# Metroband_1_1_with_changes_-_Sheet1.net
KiCad netlist of a schematic drawn in Altium Designer
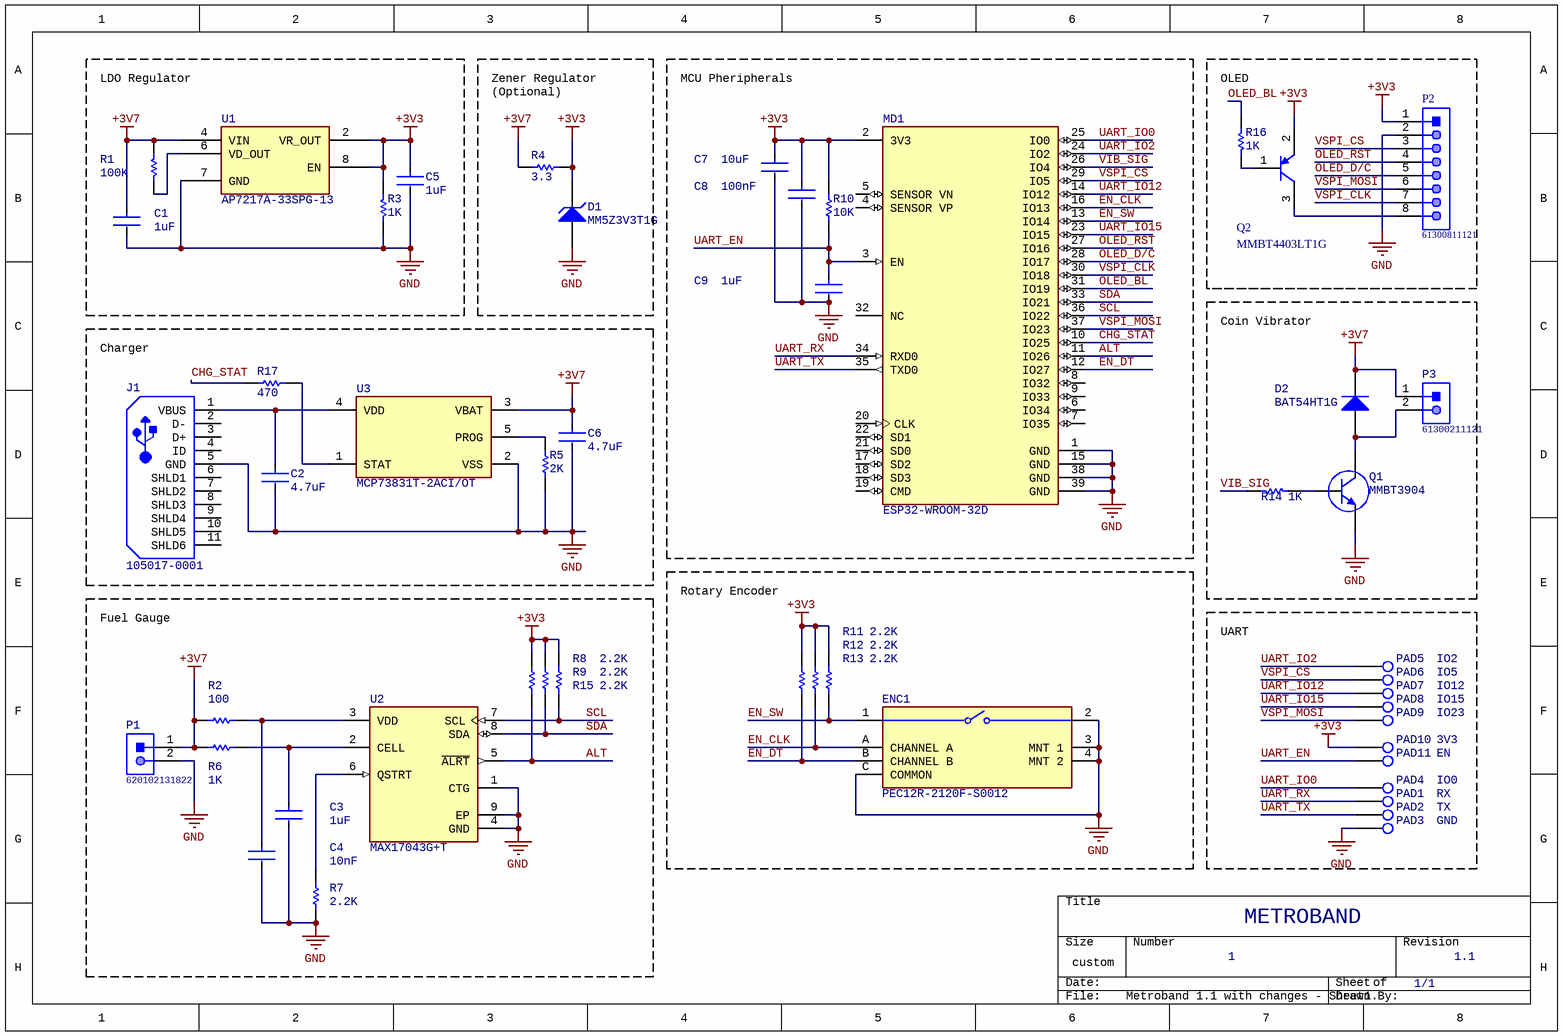
[diagram p0: Metroband 1.1 with changes - Sheet1.SchDoc]

(export (version "E")
  (design (tool "Eeschema 10.0.6"))
  (components
    (comp (ref "C1")
      (value "1uF")
      (footprint "FP-GRM21B-0_15-IPC_C")
      (description "Chip Multilayer Ceramic Capacitors for General Purpose, 0805, 1uF, X5R, 15%, 10%, 25V")
      (fields (field (name "VOLTAGE") "25V") (field (name "TOLERANCE") "10%"))
      (libsource (lib "Altium Content Vault") (part "b4654b650e69147ec39a6b967a45e02"))
    )
    (comp (ref "C2")
      (value "4.7uF")
      (footprint "FP-GRM21B-0_15-IPC_C")
      (description "Chip Multilayer Ceramic Capacitors for General Purpose, 0805, 4.7uF, X5R, 15%, 10%, 25V")
      (fields (field (name "VOLTAGE") "25V") (field (name "TOLERANCE") "10%"))
      (libsource (lib "Altium Content Vault") (part "b4654b650e69147ec39a6b967a45e02"))
    )
    (comp (ref "C3")
      (value "1uF")
      (footprint "FP-GRM21B-0_15-IPC_C")
      (description "Chip Multilayer Ceramic Capacitors for General Purpose, 0805, 1uF, X5R, 15%, 10%, 25V")
      (fields (field (name "VOLTAGE") "25V") (field (name "TOLERANCE") "10%"))
      (libsource (lib "Altium Content Vault") (part "b4654b650e69147ec39a6b967a45e02"))
    )
    (comp (ref "C4")
      (value "10nF")
      (footprint "FP-GRM21B-0_15-IPC_C")
      (description "Chip Multilayer Ceramic Capacitors for General Purpose, 0805, 10nF, X5R, 15%, 10%, 25V")
      (fields (field (name "VOLTAGE") "25V") (field (name "TOLERANCE") "10%"))
      (libsource (lib "Altium Content Vault") (part "b4654b650e69147ec39a6b967a45e02"))
    )
    (comp (ref "C5")
      (value "1uF")
      (footprint "FP-GRM21B-0_15-IPC_C")
      (description "Chip Multilayer Ceramic Capacitors for General Purpose, 0805, 1uF, X5R, 15%, 10%, 25V")
      (fields (field (name "VOLTAGE") "25V") (field (name "TOLERANCE") "10%"))
      (libsource (lib "Altium Content Vault") (part "b4654b650e69147ec39a6b967a45e02"))
    )
    (comp (ref "C6")
      (value "4.7uF")
      (footprint "FP-GRM21B-0_15-IPC_C")
      (description "Chip Multilayer Ceramic Capacitors for General Purpose, 0805, 4.7uF, X5R, 15%, 10%, 25V")
      (fields (field (name "VOLTAGE") "25V") (field (name "TOLERANCE") "10%"))
      (libsource (lib "Altium Content Vault") (part "b4654b650e69147ec39a6b967a45e02"))
    )
    (comp (ref "C7")
      (value "10uF")
      (footprint "FP-GRM21B-0_15-IPC_C")
      (description "Chip Multilayer Ceramic Capacitors for General Purpose, 0805, 10uF, X5R, 15%, 10%, 25V")
      (fields (field (name "VOLTAGE") "25V") (field (name "TOLERANCE") "10%"))
      (libsource (lib "Altium Content Vault") (part "b4654b650e69147ec39a6b967a45e02"))
    )
    (comp (ref "C8")
      (value "100nF")
      (footprint "FP-GRM21B-0_15-IPC_C")
      (description "Chip Multilayer Ceramic Capacitors for General Purpose, 0805, 100nF, X5R, 15%, 10%, 25V")
      (fields (field (name "VOLTAGE") "25V") (field (name "TOLERANCE") "10%"))
      (libsource (lib "Altium Content Vault") (part "b4654b650e69147ec39a6b967a45e02"))
    )
    (comp (ref "C9")
      (value "1uF")
      (footprint "FP-GRM21B-0_15-IPC_C")
      (description "Chip Multilayer Ceramic Capacitors for General Purpose, 0805, 1uF, X5R, 15%, 10%, 25V")
      (fields (field (name "VOLTAGE") "25V") (field (name "TOLERANCE") "10%"))
      (libsource (lib "Altium Content Vault") (part "b4654b650e69147ec39a6b967a45e02"))
    )
    (comp (ref "D1")
      (value "MM5Z3V3T1G")
      (footprint "ONSC-SOD-523-2-502-01_V")
      (description "Zener Voltage Regulator, 500 mW, 2-Pin SOD-523, Pb-Free, Tape and Reel")
      (fields (field (name "MANUFACTURER") "On Semiconductor"))
      (libsource (lib "Altium Content Vault") (part "ONSC-K1A2-2"))
    )
    (comp (ref "D2")
      (value "BAT54HT1G")
      (footprint "ONSC-SOD-323-2-477-02_V")
      (description "Schottky Barrier Diode, 2-Pin SOD-323, Pb-Free, Tape and Reel")
      (fields (field (name "MANUFACTURER") "On Semiconductor"))
      (libsource (lib "Altium Content Vault") (part "ONSC-D-K1A2-2"))
    )
    (comp (ref "ENC1")
      (value "PEC12R-2120F-S0012")
      (footprint "FP-PEC12R-2120F-S0012-MFG")
      (description "ROTARY ENCODER MECHANICAL 12PPR")
      (libsource (lib "Altium Content Vault") (part "b5b8d557d67ab9c2afb5dfea282e03e"))
    )
    (comp (ref "J1")
      (value "105017-0001")
      (footprint "USB-MICRO-B_V")
      (fields (field (name "MANUFACTURER") "Molex"))
      (libsource (lib "Altium Content Vault") (part "USB-5-6SHLD"))
    )
    (comp (ref "MD1")
      (value "ESP32-WROOM-32D")
      (footprint "FP-ESP32-WROOM-32D-MFG")
      (description "WIFI MODULE 32MBITS SPI FLASH")
      (fields
        (field (name "OCTOPART") "https://octopart.com/esp32-wroom-32d-espressif+systems-91040050")
        (field (name "MANUFACTURER") "Espressif Systems")
      )
      (libsource (lib "Altium Content Vault") (part "a031a76f8c27026a7a7f4657ff233a3"))
    )
    (comp (ref "P1")
      (value "620102131822")
      (footprint "620102131822")
      (description "Male Shrouded Header WR-WTB, SMT, Right Angled, pitch 2 mm, 1 x 2 position")
      (fields (field (name "MANUFACTURER") "Wurth Elektronik") (field (name "PUBLISHER") "WurthElektronik"))
      (libsource (lib "Altium Content Vault") (part "WE-CN-1P-M-R2"))
    )
    (comp (ref "P2")
      (value "61300811121")
      (footprint "61300811121")
      (description "THT Vertical Pin Header WR-PHD, Pitch 2.54 mm, Single Row, 8 pins")
      (fields (field (name "MANUFACTURER") "Wurth Elektronik") (field (name "PUBLISHER") "WurthElektronik"))
      (libsource (lib "Altium Content Vault") (part "WE-CN-1P-M-R8"))
    )
    (comp (ref "P3")
      (value "61300211121")
      (footprint "61300211121")
      (description "THT Vertical Pin Header WR-PHD, Pitch 2.54 mm, Single Row, 2 pins")
      (fields (field (name "MANUFACTURER") "Wurth Elektronik") (field (name "PUBLISHER") "WurthElektronik"))
      (libsource (lib "") (part "WE-CN-1P-M-R2_1"))
    )
    (comp (ref "PAD1")
      (value "RX")
      (footprint "PAD-Footprint-1")
      (description "Wirepad")
      (libsource (lib "UoM") (part "PAD-Symbol-1"))
    )
    (comp (ref "PAD2")
      (value "TX")
      (footprint "PAD-Footprint-1")
      (description "Wirepad")
      (libsource (lib "UoM") (part "PAD-Symbol-1"))
    )
    (comp (ref "PAD3")
      (value "GND")
      (footprint "PAD-Footprint-1")
      (description "Wirepad")
      (libsource (lib "UoM") (part "PAD-Symbol-1"))
    )
    (comp (ref "PAD4")
      (value "IO0")
      (footprint "PAD-Footprint-1")
      (description "Wirepad")
      (libsource (lib "UoM") (part "PAD-Symbol-1"))
    )
    (comp (ref "PAD5")
      (value "IO2")
      (footprint "PAD-Footprint-1")
      (description "Wirepad")
      (libsource (lib "UoM") (part "PAD-Symbol-1"))
    )
    (comp (ref "PAD6")
      (value "IO5")
      (footprint "PAD-Footprint-1")
      (description "Wirepad")
      (libsource (lib "UoM") (part "PAD-Symbol-1"))
    )
    (comp (ref "PAD7")
      (value "IO12")
      (footprint "PAD-Footprint-1")
      (description "Wirepad")
      (libsource (lib "UoM") (part "PAD-Symbol-1"))
    )
    (comp (ref "PAD8")
      (value "IO15")
      (footprint "PAD-Footprint-1")
      (description "Wirepad")
      (libsource (lib "UoM") (part "PAD-Symbol-1"))
    )
    (comp (ref "PAD9")
      (value "IO23")
      (footprint "PAD-Footprint-1")
      (description "Wirepad")
      (libsource (lib "UoM") (part "PAD-Symbol-1"))
    )
    (comp (ref "PAD10")
      (value "3V3")
      (footprint "PAD-Footprint-1")
      (description "Wirepad")
      (libsource (lib "UoM") (part "PAD-Symbol-1"))
    )
    (comp (ref "PAD11")
      (value "EN")
      (footprint "PAD-Footprint-1")
      (description "Wirepad")
      (libsource (lib "UoM") (part "PAD-Symbol-1"))
    )
    (comp (ref "Q1")
      (value "MMBT3904")
      (footprint "NXP-SOT23-3_V")
      (description "TRANSISTOR, NPN, REEL 3K")
      (libsource (lib "UoM") (part "TRANS-NPN-3"))
    )
    (comp (ref "Q2")
      (value "MMBT4403LT1G")
      (footprint "ONSC-SOT-23-3-318-08_V")
      (description "Switching Transistor, PNP Silicon, 3-Pin SOT-23, Pb-Free, Tape and Reel")
      (fields (field (name "MANUFACTURER") "On Semiconductor"))
      (libsource (lib "Altium Content Vault") (part "ONSC-PNP-B1E2C3-3"))
    )
    (comp (ref "R1")
      (value "100K")
      (footprint "RESC1609X50X30NL8T20")
      (description "Chip Resistor, 100K Ohm, Jumper, 100 mW, -55 to 155 degC, 0603 (1608 Metric), RoHS, Tape and Reel")
      (fields (field (name "MANUFACTURER") "Vishay Semiconductor"))
      (libsource (lib "Altium Content Vault") (part "RES-2"))
    )
    (comp (ref "R2")
      (value "100")
      (footprint "RESC1609X50X30NL8T20")
      (description "Chip Resistor, 100 Ohm, Jumper, 100 mW, -55 to 155 degC, 0603 (1608 Metric), RoHS, Tape and Reel")
      (fields (field (name "MANUFACTURER") "Vishay Semiconductor"))
      (libsource (lib "Altium Content Vault") (part "RES-2"))
    )
    (comp (ref "R3")
      (value "1K")
      (footprint "RESC1609X50X30NL8T20")
      (description "Chip Resistor, 1K Ohm, Jumper, 100 mW, -55 to 155 degC, 0603 (1608 Metric), RoHS, Tape and Reel")
      (fields (field (name "MANUFACTURER") "Vishay Semiconductor"))
      (libsource (lib "Altium Content Vault") (part "RES-2"))
    )
    (comp (ref "R4")
      (value "3.3")
      (footprint "RESC1609X50X30NL8T20")
      (description "Chip Resistor, 3.3 Ohm, Jumper, 100 mW, -55 to 155 degC, 0603 (1608 Metric), RoHS, Tape and Reel")
      (fields (field (name "MANUFACTURER") "Vishay Semiconductor"))
      (libsource (lib "Altium Content Vault") (part "RES-2"))
    )
    (comp (ref "R5")
      (value "2K")
      (footprint "RESC1609X50X30NL8T20")
      (description "Chip Resistor, 2K Ohm, Jumper, 100 mW, -55 to 155 degC, 0603 (1608 Metric), RoHS, Tape and Reel")
      (fields (field (name "MANUFACTURER") "Vishay Semiconductor"))
      (libsource (lib "Altium Content Vault") (part "RES-2"))
    )
    (comp (ref "R6")
      (value "1K")
      (footprint "RESC1609X50X30NL8T20")
      (description "Chip Resistor, 1K Ohm, Jumper, 100 mW, -55 to 155 degC, 0603 (1608 Metric), RoHS, Tape and Reel")
      (fields (field (name "MANUFACTURER") "Vishay Semiconductor"))
      (libsource (lib "Altium Content Vault") (part "RES-2"))
    )
    (comp (ref "R7")
      (value "2.2K")
      (footprint "RESC1609X50X30NL8T20")
      (description "Chip Resistor, 0 Ohm, Jumper, 100 mW, -55 to 155 degC, 0603 (1608 Metric), RoHS, Tape and Reel")
      (fields (field (name "MANUFACTURER") "Vishay Semiconductor"))
      (libsource (lib "Altium Content Vault") (part "RES-2"))
    )
    (comp (ref "R8")
      (value "2.2K")
      (footprint "RESC1609X50X30NL8T20")
      (description "Chip Resistor, 2.2K Ohm, Jumper, 100 mW, -55 to 155 degC, 0603 (1608 Metric), RoHS, Tape and Reel")
      (fields (field (name "MANUFACTURER") "Vishay Semiconductor"))
      (libsource (lib "Altium Content Vault") (part "RES-2"))
    )
    (comp (ref "R9")
      (value "2.2K")
      (footprint "RESC1609X50X30NL8T20")
      (description "Chip Resistor, 2.2K Ohm, Jumper, 100 mW, -55 to 155 degC, 0603 (1608 Metric), RoHS, Tape and Reel")
      (fields (field (name "MANUFACTURER") "Vishay Semiconductor"))
      (libsource (lib "Altium Content Vault") (part "RES-2"))
    )
    (comp (ref "R10")
      (value "10K")
      (footprint "RESC1609X50X30NL8T20")
      (description "Chip Resistor, 10K Ohm, Jumper, 100 mW, -55 to 155 degC, 0603 (1608 Metric), RoHS, Tape and Reel")
      (fields (field (name "MANUFACTURER") "Vishay Semiconductor"))
      (libsource (lib "Altium Content Vault") (part "RES-2"))
    )
    (comp (ref "R11")
      (value "2.2K")
      (footprint "RESC1609X50X30NL8T20")
      (description "Chip Resistor, 2.2K Ohm, Jumper, 100 mW, -55 to 155 degC, 0603 (1608 Metric), RoHS, Tape and Reel")
      (fields (field (name "MANUFACTURER") "Vishay Semiconductor"))
      (libsource (lib "Altium Content Vault") (part "RES-2"))
    )
    (comp (ref "R12")
      (value "2.2K")
      (footprint "RESC1609X50X30NL8T20")
      (description "Chip Resistor, 2.2K Ohm, Jumper, 100 mW, -55 to 155 degC, 0603 (1608 Metric), RoHS, Tape and Reel")
      (fields (field (name "MANUFACTURER") "Vishay Semiconductor"))
      (libsource (lib "Altium Content Vault") (part "RES-2"))
    )
    (comp (ref "R13")
      (value "2.2K")
      (footprint "RESC1609X50X30NL8T20")
      (description "Chip Resistor, 2.2K Ohm, Jumper, 100 mW, -55 to 155 degC, 0603 (1608 Metric), RoHS, Tape and Reel")
      (fields (field (name "MANUFACTURER") "Vishay Semiconductor"))
      (libsource (lib "Altium Content Vault") (part "RES-2"))
    )
    (comp (ref "R14")
      (value "1K")
      (footprint "RESC1609X50X30NL8T20")
      (description "Chip Resistor, 1K Ohm, Jumper, 100 mW, -55 to 155 degC, 0603 (1608 Metric), RoHS, Tape and Reel")
      (fields (field (name "MANUFACTURER") "Vishay Semiconductor"))
      (libsource (lib "Altium Content Vault") (part "RES-2"))
    )
    (comp (ref "R15")
      (value "2.2K")
      (footprint "RESC1609X50X30NL8T20")
      (description "Chip Resistor, 2.2K Ohm, Jumper, 100 mW, -55 to 155 degC, 0603 (1608 Metric), RoHS, Tape and Reel")
      (fields (field (name "MANUFACTURER") "Vishay Semiconductor"))
      (libsource (lib "Altium Content Vault") (part "RES-2"))
    )
    (comp (ref "R16")
      (value "1K")
      (footprint "RESC1609X50X30NL8T20")
      (description "Chip Resistor, 1K Ohm, Jumper, 100 mW, -55 to 155 degC, 0603 (1608 Metric), RoHS, Tape and Reel")
      (fields (field (name "MANUFACTURER") "Vishay Semiconductor"))
      (libsource (lib "Altium Content Vault") (part "RES-2"))
    )
    (comp (ref "R17")
      (value "470")
      (footprint "RESC1609X50X30NL8T20")
      (description "Chip Resistor, 2K Ohm, Jumper, 100 mW, -55 to 155 degC, 0603 (1608 Metric), RoHS, Tape and Reel")
      (fields (field (name "MANUFACTURER") "Vishay Semiconductor"))
      (libsource (lib "Altium Content Vault") (part "RES-2"))
    )
    (comp (ref "U1")
      (value "AP7217A-33SPG-13")
      (footprint "AP7217A-33SPG-13-Footprint-1")
      (description "Fixed Positive LDO Regulator, 3.3V, 0.9V Dropout, CMOS, PDSO8")
      (libsource (lib "UoM") (part "AP7217A-33SPG-13-Symbol-1"))
    )
    (comp (ref "U2")
      (value "MAX17043G+T")
      (footprint "FP-T823-1-MFG")
      (description "IC 2-WIRE FG MODEL GAUGE LO BATT")
      (fields
        (field (name "MANUFACTURER") "Maxim")
        (field (name "OCTOPART") "https://octopart.com/max17043g%2Bt-maxim+integrated-43979038")
      )
      (libsource (lib "Altium Content Vault") (part "35642440c5a18a865b7fad9439d5373"))
    )
    (comp (ref "U3")
      (value "MCP73831T-2ACI/OT")
      (footprint "FP-C04-091-OT-IPC_A")
      (description "IC CONTROLLR LI-ION 4.2V SOT23-5")
      (libsource (lib "Altium Content Vault") (part "61f5a3bb3429d9e0caadea342aa3b19"))
    )
  )
  (nets
    (net (code "1") (name "+3V3") (class "Default")
      (node (ref "C5") (pin "1") (pinfunction "1_1") (pintype "passive"))
      (node (ref "C7") (pin "1") (pinfunction "1_1") (pintype "passive"))
      (node (ref "C8") (pin "1") (pinfunction "1_1") (pintype "passive"))
      (node (ref "D1") (pin "1") (pinfunction "K_1") (pintype "passive"))
      (node (ref "MD1") (pin "2") (pinfunction "3V3_2") (pintype "power_in"))
      (node (ref "P2") (pin "1") (pinfunction "1_1") (pintype "passive"))
      (node (ref "PAD10") (pin "1") (pintype "passive"))
      (node (ref "Q2") (pin "2") (pinfunction "E_2") (pintype "passive"))
      (node (ref "R10") (pin "2") (pinfunction "2_2") (pintype "passive"))
      (node (ref "R11") (pin "2") (pinfunction "2_2") (pintype "passive"))
      (node (ref "R12") (pin "2") (pinfunction "2_2") (pintype "passive"))
      (node (ref "R13") (pin "2") (pinfunction "2_2") (pintype "passive"))
      (node (ref "R15") (pin "2") (pinfunction "2_2") (pintype "passive"))
      (node (ref "R3") (pin "2") (pinfunction "2_2") (pintype "passive"))
      (node (ref "R4") (pin "2") (pinfunction "2_2") (pintype "passive"))
      (node (ref "R8") (pin "2") (pinfunction "2_2") (pintype "passive"))
      (node (ref "R9") (pin "2") (pinfunction "2_2") (pintype "passive"))
      (node (ref "U1") (pin "2") (pinfunction "VR_OUT_2") (pintype "passive"))
      (node (ref "U1") (pin "8") (pinfunction "EN_8") (pintype "passive"))
    )
    (net (code "2") (name "+3V7") (class "Default")
      (node (ref "C1") (pin "1") (pinfunction "1_1") (pintype "passive"))
      (node (ref "C6") (pin "1") (pinfunction "1_1") (pintype "passive"))
      (node (ref "D2") (pin "1") (pinfunction "K_1") (pintype "passive"))
      (node (ref "P1") (pin "1") (pinfunction "1_1") (pintype "passive"))
      (node (ref "P3") (pin "1") (pinfunction "1_1") (pintype "passive"))
      (node (ref "R1") (pin "2") (pinfunction "2_2") (pintype "passive"))
      (node (ref "R2") (pin "2") (pinfunction "2_2") (pintype "passive"))
      (node (ref "R4") (pin "1") (pinfunction "1_1") (pintype "passive"))
      (node (ref "R6") (pin "2") (pinfunction "2_2") (pintype "passive"))
      (node (ref "U1") (pin "4") (pinfunction "VIN_4") (pintype "passive"))
      (node (ref "U3") (pin "3") (pinfunction "VBAT_3") (pintype "power_in"))
    )
    (net (code "3") (name "/ALT") (class "Default")
      (node (ref "MD1") (pin "11") (pinfunction "IO26_11") (pintype "bidirectional"))
      (node (ref "R8") (pin "1") (pinfunction "1_1") (pintype "passive"))
      (node (ref "U2") (pin "5") (pinfunction "~{ALRT}_5") (pintype "output"))
    )
    (net (code "4") (name "/CHG_STAT") (class "Default")
      (node (ref "MD1") (pin "10") (pinfunction "IO25_10") (pintype "bidirectional"))
      (node (ref "R17") (pin "2") (pinfunction "2_2") (pintype "passive"))
    )
    (net (code "5") (name "/EN_CLK") (class "Default")
      (node (ref "ENC1") (pin "A") (pinfunction "CHANNEL_A_A") (pintype "passive"))
      (node (ref "MD1") (pin "16") (pinfunction "IO13_16") (pintype "bidirectional"))
      (node (ref "R12") (pin "1") (pinfunction "1_1") (pintype "passive"))
    )
    (net (code "6") (name "/EN_DT") (class "Default")
      (node (ref "ENC1") (pin "B") (pinfunction "CHANNEL_B_B") (pintype "passive"))
      (node (ref "MD1") (pin "12") (pinfunction "IO27_12") (pintype "bidirectional"))
      (node (ref "R11") (pin "1") (pinfunction "1_1") (pintype "passive"))
    )
    (net (code "7") (name "/EN_SW") (class "Default")
      (node (ref "ENC1") (pin "1") (pinfunction "1_1") (pintype "passive"))
      (node (ref "MD1") (pin "13") (pinfunction "IO14_13") (pintype "bidirectional"))
      (node (ref "R13") (pin "1") (pinfunction "1_1") (pintype "passive"))
    )
    (net (code "8") (name "/OLED_BL") (class "Default")
      (node (ref "MD1") (pin "31") (pinfunction "IO19_31") (pintype "bidirectional"))
      (node (ref "R16") (pin "2") (pinfunction "2_2") (pintype "passive"))
    )
    (net (code "9") (name "/OLED_D{slash}C") (class "Default")
      (node (ref "MD1") (pin "28") (pinfunction "IO17_28") (pintype "bidirectional"))
      (node (ref "P2") (pin "5") (pinfunction "5_5") (pintype "passive"))
    )
    (net (code "10") (name "/OLED_RST") (class "Default")
      (node (ref "MD1") (pin "27") (pinfunction "IO16_27") (pintype "bidirectional"))
      (node (ref "P2") (pin "4") (pinfunction "4_4") (pintype "passive"))
    )
    (net (code "11") (name "/SCL") (class "Default")
      (node (ref "MD1") (pin "36") (pinfunction "IO22_36") (pintype "bidirectional"))
      (node (ref "R15") (pin "1") (pinfunction "1_1") (pintype "passive"))
      (node (ref "U2") (pin "7") (pinfunction "SCL_7") (pintype "input"))
    )
    (net (code "12") (name "/SDA") (class "Default")
      (node (ref "MD1") (pin "33") (pinfunction "IO21_33") (pintype "bidirectional"))
      (node (ref "R9") (pin "1") (pinfunction "1_1") (pintype "passive"))
      (node (ref "U2") (pin "8") (pinfunction "SDA_8") (pintype "bidirectional"))
    )
    (net (code "13") (name "/UART_EN") (class "Default")
      (node (ref "C9") (pin "1") (pinfunction "1_1") (pintype "passive"))
      (node (ref "MD1") (pin "3") (pinfunction "EN_3") (pintype "input"))
      (node (ref "PAD11") (pin "1") (pintype "passive"))
      (node (ref "R10") (pin "1") (pinfunction "1_1") (pintype "passive"))
    )
    (net (code "14") (name "/UART_IO0") (class "Default")
      (node (ref "MD1") (pin "25") (pinfunction "IO0_25") (pintype "bidirectional"))
      (node (ref "PAD4") (pin "1") (pintype "passive"))
    )
    (net (code "15") (name "/UART_IO2") (class "Default")
      (node (ref "MD1") (pin "24") (pinfunction "IO2_24") (pintype "bidirectional"))
      (node (ref "PAD5") (pin "1") (pintype "passive"))
    )
    (net (code "16") (name "/UART_IO12") (class "Default")
      (node (ref "MD1") (pin "14") (pinfunction "IO12_14") (pintype "bidirectional"))
      (node (ref "PAD7") (pin "1") (pintype "passive"))
    )
    (net (code "17") (name "/UART_IO15") (class "Default")
      (node (ref "MD1") (pin "23") (pinfunction "IO15_23") (pintype "bidirectional"))
      (node (ref "PAD8") (pin "1") (pintype "passive"))
    )
    (net (code "18") (name "/UART_RX") (class "Default")
      (node (ref "MD1") (pin "34") (pinfunction "RXD0_34") (pintype "input"))
      (node (ref "PAD1") (pin "1") (pintype "passive"))
    )
    (net (code "19") (name "/UART_TX") (class "Default")
      (node (ref "MD1") (pin "35") (pinfunction "TXD0_35") (pintype "output"))
      (node (ref "PAD2") (pin "1") (pintype "passive"))
    )
    (net (code "20") (name "/VIB_SIG") (class "Default")
      (node (ref "MD1") (pin "26") (pinfunction "IO4_26") (pintype "bidirectional"))
      (node (ref "R14") (pin "2") (pinfunction "2_2") (pintype "passive"))
    )
    (net (code "21") (name "/VSPI_CLK") (class "Default")
      (node (ref "MD1") (pin "30") (pinfunction "IO18_30") (pintype "bidirectional"))
      (node (ref "P2") (pin "7") (pinfunction "7_7") (pintype "passive"))
    )
    (net (code "22") (name "/VSPI_CS") (class "Default")
      (node (ref "MD1") (pin "29") (pinfunction "IO5_29") (pintype "bidirectional"))
      (node (ref "P2") (pin "3") (pinfunction "3_3") (pintype "passive"))
      (node (ref "PAD6") (pin "1") (pintype "passive"))
    )
    (net (code "23") (name "/VSPI_MOSI") (class "Default")
      (node (ref "MD1") (pin "37") (pinfunction "IO23_37") (pintype "bidirectional"))
      (node (ref "P2") (pin "6") (pinfunction "6_6") (pintype "passive"))
      (node (ref "PAD9") (pin "1") (pintype "passive"))
    )
    (net (code "24") (name "GND") (class "Default")
      (node (ref "C1") (pin "2") (pinfunction "2_2") (pintype "passive"))
      (node (ref "C2") (pin "2") (pinfunction "2_2") (pintype "passive"))
      (node (ref "C3") (pin "2") (pinfunction "2_2") (pintype "passive"))
      (node (ref "C4") (pin "2") (pinfunction "2_2") (pintype "passive"))
      (node (ref "C5") (pin "2") (pinfunction "2_2") (pintype "passive"))
      (node (ref "C6") (pin "2") (pinfunction "2_2") (pintype "passive"))
      (node (ref "C7") (pin "2") (pinfunction "2_2") (pintype "passive"))
      (node (ref "C8") (pin "2") (pinfunction "2_2") (pintype "passive"))
      (node (ref "C9") (pin "2") (pinfunction "2_2") (pintype "passive"))
      (node (ref "D1") (pin "2") (pinfunction "A_2") (pintype "passive"))
      (node (ref "ENC1") (pin "2") (pinfunction "2_2") (pintype "passive"))
      (node (ref "ENC1") (pin "3") (pinfunction "MNT_1_3") (pintype "passive"))
      (node (ref "ENC1") (pin "4") (pinfunction "MNT_2_4") (pintype "passive"))
      (node (ref "ENC1") (pin "C") (pinfunction "COMMON_C") (pintype "passive"))
      (node (ref "J1") (pin "5") (pinfunction "GND_5") (pintype "passive"))
      (node (ref "MD1") (pin "1") (pinfunction "GND_1") (pintype "power_in"))
      (node (ref "MD1") (pin "15") (pinfunction "GND_15") (pintype "power_in"))
      (node (ref "MD1") (pin "38") (pinfunction "GND_38") (pintype "power_in"))
      (node (ref "MD1") (pin "39") (pinfunction "GND_39") (pintype "power_in"))
      (node (ref "P1") (pin "2") (pinfunction "2_2") (pintype "passive"))
      (node (ref "P2") (pin "2") (pinfunction "2_2") (pintype "passive"))
      (node (ref "PAD3") (pin "1") (pintype "passive"))
      (node (ref "Q1") (pin "2") (pinfunction "E_2") (pintype "passive"))
      (node (ref "R3") (pin "1") (pinfunction "1_1") (pintype "passive"))
      (node (ref "R5") (pin "1") (pinfunction "1_1") (pintype "passive"))
      (node (ref "R7") (pin "1") (pinfunction "1_1") (pintype "passive"))
      (node (ref "U1") (pin "7") (pinfunction "GND_7") (pintype "passive"))
      (node (ref "U2") (pin "1") (pinfunction "CTG_1") (pintype "power_in"))
      (node (ref "U2") (pin "4") (pinfunction "GND_4") (pintype "power_in"))
      (node (ref "U2") (pin "9") (pinfunction "EP_9") (pintype "power_in"))
      (node (ref "U3") (pin "2") (pinfunction "VSS_2") (pintype "power_in"))
    )
    (net (code "25") (name "Net-(D2-A)") (class "Default")
      (node (ref "D2") (pin "2") (pinfunction "A_2") (pintype "passive"))
      (node (ref "P3") (pin "2") (pinfunction "2_2") (pintype "passive"))
      (node (ref "Q1") (pin "3") (pinfunction "C_3") (pintype "passive"))
    )
    (net (code "26") (name "Net-(J1-VBUS)") (class "Default")
      (node (ref "C2") (pin "1") (pinfunction "1_1") (pintype "passive"))
      (node (ref "J1") (pin "1") (pinfunction "VBUS_1") (pintype "passive"))
      (node (ref "U3") (pin "4") (pinfunction "VDD_4") (pintype "power_in"))
    )
    (net (code "27") (name "Net-(Q1-B)") (class "Default")
      (node (ref "Q1") (pin "1") (pinfunction "B_1") (pintype "passive"))
      (node (ref "R14") (pin "1") (pinfunction "1_1") (pintype "passive"))
    )
    (net (code "28") (name "Net-(Q2-B)") (class "Default")
      (node (ref "Q2") (pin "1") (pinfunction "B_1") (pintype "passive"))
      (node (ref "R16") (pin "1") (pinfunction "1_1") (pintype "passive"))
    )
    (net (code "29") (name "Net-(Q2-C)") (class "Default")
      (node (ref "P2") (pin "8") (pinfunction "8_8") (pintype "passive"))
      (node (ref "Q2") (pin "3") (pinfunction "C_3") (pintype "passive"))
    )
    (net (code "30") (name "Net-(U1-VD_OUT)") (class "Default")
      (node (ref "R1") (pin "1") (pinfunction "1_1") (pintype "passive"))
      (node (ref "U1") (pin "6") (pinfunction "VD_OUT_6") (pintype "passive"))
    )
    (net (code "31") (name "Net-(U2-CELL)") (class "Default")
      (node (ref "C3") (pin "1") (pinfunction "1_1") (pintype "passive"))
      (node (ref "R6") (pin "1") (pinfunction "1_1") (pintype "passive"))
      (node (ref "U2") (pin "2") (pinfunction "CELL_2") (pintype "passive"))
    )
    (net (code "32") (name "Net-(U2-QSTRT)") (class "Default")
      (node (ref "R7") (pin "2") (pinfunction "2_2") (pintype "passive"))
      (node (ref "U2") (pin "6") (pinfunction "QSTRT_6") (pintype "input"))
    )
    (net (code "33") (name "Net-(U2-VDD)") (class "Default")
      (node (ref "C4") (pin "1") (pinfunction "1_1") (pintype "passive"))
      (node (ref "R2") (pin "1") (pinfunction "1_1") (pintype "passive"))
      (node (ref "U2") (pin "3") (pinfunction "VDD_3") (pintype "power_in"))
    )
    (net (code "34") (name "Net-(U3-PROG)") (class "Default")
      (node (ref "R5") (pin "2") (pinfunction "2_2") (pintype "passive"))
      (node (ref "U3") (pin "5") (pinfunction "PROG_5") (pintype "passive"))
    )
    (net (code "35") (name "Net-(U3-STAT)") (class "Default")
      (node (ref "R17") (pin "1") (pinfunction "1_1") (pintype "passive"))
      (node (ref "U3") (pin "1") (pinfunction "STAT_1") (pintype "passive"))
    )
    (net (code "36") (name "unconnected-(J1-D+-Pad3)") (class "Default")
      (node (ref "J1") (pin "3") (pinfunction "D+_3") (pintype "passive"))
    )
    (net (code "37") (name "unconnected-(J1-D--Pad2)") (class "Default")
      (node (ref "J1") (pin "2") (pinfunction "D-_2") (pintype "passive"))
    )
    (net (code "38") (name "unconnected-(J1-ID-Pad4)") (class "Default")
      (node (ref "J1") (pin "4") (pinfunction "ID_4") (pintype "passive"))
    )
    (net (code "39") (name "unconnected-(J1-SHLD1-Pad6)") (class "Default")
      (node (ref "J1") (pin "6") (pinfunction "SHLD1_6") (pintype "passive"))
    )
    (net (code "40") (name "unconnected-(J1-SHLD2-Pad7)") (class "Default")
      (node (ref "J1") (pin "7") (pinfunction "SHLD2_7") (pintype "passive"))
    )
    (net (code "41") (name "unconnected-(J1-SHLD3-Pad8)") (class "Default")
      (node (ref "J1") (pin "8") (pinfunction "SHLD3_8") (pintype "passive"))
    )
    (net (code "42") (name "unconnected-(J1-SHLD4-Pad9)") (class "Default")
      (node (ref "J1") (pin "9") (pinfunction "SHLD4_9") (pintype "passive"))
    )
    (net (code "43") (name "unconnected-(J1-SHLD5-Pad10)") (class "Default")
      (node (ref "J1") (pin "10") (pinfunction "SHLD5_10") (pintype "passive"))
    )
    (net (code "44") (name "unconnected-(J1-SHLD6-Pad11)") (class "Default")
      (node (ref "J1") (pin "11") (pinfunction "SHLD6_11") (pintype "passive"))
    )
    (net (code "45") (name "unconnected-(MD1-CLK-Pad20)") (class "Default")
      (node (ref "MD1") (pin "20") (pinfunction "CLK_20") (pintype "input"))
    )
    (net (code "46") (name "unconnected-(MD1-CMD-Pad19)") (class "Default")
      (node (ref "MD1") (pin "19") (pinfunction "CMD_19") (pintype "bidirectional"))
    )
    (net (code "47") (name "unconnected-(MD1-IO32-Pad8)") (class "Default")
      (node (ref "MD1") (pin "8") (pinfunction "IO32_8") (pintype "bidirectional"))
    )
    (net (code "48") (name "unconnected-(MD1-IO33-Pad9)") (class "Default")
      (node (ref "MD1") (pin "9") (pinfunction "IO33_9") (pintype "bidirectional"))
    )
    (net (code "49") (name "unconnected-(MD1-IO34-Pad6)") (class "Default")
      (node (ref "MD1") (pin "6") (pinfunction "IO34_6") (pintype "bidirectional"))
    )
    (net (code "50") (name "unconnected-(MD1-IO35-Pad7)") (class "Default")
      (node (ref "MD1") (pin "7") (pinfunction "IO35_7") (pintype "bidirectional"))
    )
    (net (code "51") (name "unconnected-(MD1-NC-Pad32)") (class "Default")
      (node (ref "MD1") (pin "32") (pinfunction "NC_32") (pintype "passive"))
    )
    (net (code "52") (name "unconnected-(MD1-SD0-Pad21)") (class "Default")
      (node (ref "MD1") (pin "21") (pinfunction "SD0_21") (pintype "bidirectional"))
    )
    (net (code "53") (name "unconnected-(MD1-SD1-Pad22)") (class "Default")
      (node (ref "MD1") (pin "22") (pinfunction "SD1_22") (pintype "bidirectional"))
    )
    (net (code "54") (name "unconnected-(MD1-SD2-Pad17)") (class "Default")
      (node (ref "MD1") (pin "17") (pinfunction "SD2_17") (pintype "bidirectional"))
    )
    (net (code "55") (name "unconnected-(MD1-SD3-Pad18)") (class "Default")
      (node (ref "MD1") (pin "18") (pinfunction "SD3_18") (pintype "bidirectional"))
    )
    (net (code "56") (name "unconnected-(MD1-SENSOR_VN-Pad5)") (class "Default")
      (node (ref "MD1") (pin "5") (pinfunction "SENSOR_VN_5") (pintype "bidirectional"))
    )
    (net (code "57") (name "unconnected-(MD1-SENSOR_VP-Pad4)") (class "Default")
      (node (ref "MD1") (pin "4") (pinfunction "SENSOR_VP_4") (pintype "bidirectional"))
    )
  )
)
